# Netfrequency.net
KiCad netlist of a schematic drawn in EAGLE
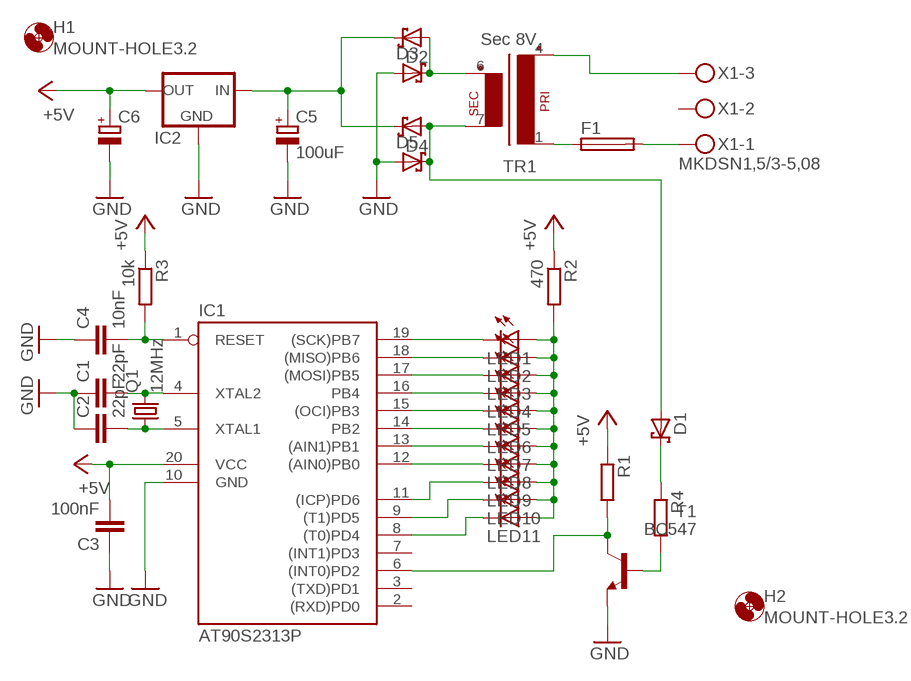
[diagram p0: schematic, sheet 1]

(export (version "E")
  (design (tool "Eeschema 10.0.6"))
  (components
    (comp (ref "C1")
      (value "22pF")
      (footprint "eagle-import:C025-025X050")
      (libsource (lib "eagle-import") (part "C-EU025-025X050"))
    )
    (comp (ref "C2")
      (value "22pF")
      (footprint "eagle-import:C025-025X050")
      (libsource (lib "eagle-import") (part "C-EU025-025X050"))
    )
    (comp (ref "C3")
      (value "100nF")
      (footprint "eagle-import:C025-025X050")
      (libsource (lib "eagle-import") (part "C-EU025-025X050"))
    )
    (comp (ref "C4")
      (value "10nF")
      (footprint "eagle-import:C025-025X050")
      (libsource (lib "eagle-import") (part "C-EU025-025X050"))
    )
    (comp (ref "C5")
      (value "100uF")
      (footprint "eagle-import:E5-8,5")
      (libsource (lib "eagle-import") (part "CPOL-EUE5-8.5"))
    )
    (comp (ref "C6")
      (value "CPOL-EUE2.5-6")
      (footprint "eagle-import:E2,5-6")
      (libsource (lib "eagle-import") (part "CPOL-EUE2.5-6"))
    )
    (comp (ref "D1")
      (value "SCHOTTKY-DIODEDO35-7")
      (footprint "eagle-import:DO35-7")
      (libsource (lib "eagle-import") (part "SCHOTTKY-DIODEDO35-7"))
    )
    (comp (ref "D2")
      (value "SCHOTTKY-DIODEDO35-7")
      (footprint "eagle-import:DO35-7")
      (libsource (lib "eagle-import") (part "SCHOTTKY-DIODEDO35-7"))
    )
    (comp (ref "D3")
      (value "SCHOTTKY-DIODEDO35-7")
      (footprint "eagle-import:DO35-7")
      (libsource (lib "eagle-import") (part "SCHOTTKY-DIODEDO35-7"))
    )
    (comp (ref "D4")
      (value "SCHOTTKY-DIODEDO35-7")
      (footprint "eagle-import:DO35-7")
      (libsource (lib "eagle-import") (part "SCHOTTKY-DIODEDO35-7"))
    )
    (comp (ref "D5")
      (value "SCHOTTKY-DIODEDO35-7")
      (footprint "eagle-import:DO35-7")
      (libsource (lib "eagle-import") (part "SCHOTTKY-DIODEDO35-7"))
    )
    (comp (ref "F1")
      (value "SH22")
      (footprint "eagle-import:SH22")
      (libsource (lib "eagle-import") (part "SH22"))
    )
    (comp (ref "H1")
      (value "MOUNT-HOLE3.2")
      (footprint "eagle-import:3,2")
      (libsource (lib "eagle-import") (part "MOUNT-HOLE3.2"))
    )
    (comp (ref "H2")
      (value "MOUNT-HOLE3.2")
      (footprint "eagle-import:3,2")
      (libsource (lib "eagle-import") (part "MOUNT-HOLE3.2"))
    )
    (comp (ref "IC1")
      (value "AT90S2313P")
      (footprint "eagle-import:DIL20")
      (libsource (lib "eagle-import") (part "AT90S2313P"))
    )
    (comp (ref "IC2")
      (value "78LXX")
      (footprint "eagle-import:78LXX")
      (libsource (lib "eagle-import") (part "78LXX"))
    )
    (comp (ref "LED1")
      (value "LEDSQR2X5")
      (footprint "eagle-import:LED2X5")
      (libsource (lib "eagle-import") (part "LEDSQR2X5"))
    )
    (comp (ref "LED2")
      (value "LEDSQR2X5")
      (footprint "eagle-import:LED2X5")
      (libsource (lib "eagle-import") (part "LEDSQR2X5"))
    )
    (comp (ref "LED3")
      (value "LEDSQR2X5")
      (footprint "eagle-import:LED2X5")
      (libsource (lib "eagle-import") (part "LEDSQR2X5"))
    )
    (comp (ref "LED4")
      (value "LEDSQR2X5")
      (footprint "eagle-import:LED2X5")
      (libsource (lib "eagle-import") (part "LEDSQR2X5"))
    )
    (comp (ref "LED5")
      (value "LEDSQR2X5")
      (footprint "eagle-import:LED2X5")
      (libsource (lib "eagle-import") (part "LEDSQR2X5"))
    )
    (comp (ref "LED6")
      (value "LEDSQR2X5")
      (footprint "eagle-import:LED2X5")
      (libsource (lib "eagle-import") (part "LEDSQR2X5"))
    )
    (comp (ref "LED7")
      (value "LEDSQR2X5")
      (footprint "eagle-import:LED2X5")
      (libsource (lib "eagle-import") (part "LEDSQR2X5"))
    )
    (comp (ref "LED8")
      (value "LEDSQR2X5")
      (footprint "eagle-import:LED2X5")
      (libsource (lib "eagle-import") (part "LEDSQR2X5"))
    )
    (comp (ref "LED9")
      (value "LEDSQR2X5")
      (footprint "eagle-import:LED2X5")
      (libsource (lib "eagle-import") (part "LEDSQR2X5"))
    )
    (comp (ref "LED10")
      (value "LEDSQR2X5")
      (footprint "eagle-import:LED2X5")
      (libsource (lib "eagle-import") (part "LEDSQR2X5"))
    )
    (comp (ref "LED11")
      (value "LEDSQR2X5")
      (footprint "eagle-import:LED2X5")
      (libsource (lib "eagle-import") (part "LEDSQR2X5"))
    )
    (comp (ref "Q1")
      (value "12MHz")
      (footprint "eagle-import:HC49_S")
      (libsource (lib "eagle-import") (part "CRYSTALHC49S"))
    )
    (comp (ref "R1")
      (value "R-EU_0204/7")
      (footprint "eagle-import:0204_7")
      (libsource (lib "eagle-import") (part "R-EU_0204/7"))
    )
    (comp (ref "R2")
      (value "470")
      (footprint "eagle-import:0204_7")
      (libsource (lib "eagle-import") (part "R-EU_0204/7"))
    )
    (comp (ref "R3")
      (value "10k")
      (footprint "eagle-import:0204_7")
      (libsource (lib "eagle-import") (part "R-EU_0204/7"))
    )
    (comp (ref "R4")
      (value "R-EU_0204/7")
      (footprint "eagle-import:0204_7")
      (libsource (lib "eagle-import") (part "R-EU_0204/7"))
    )
    (comp (ref "T1")
      (value "BC547")
      (footprint "eagle-import:TO92")
      (libsource (lib "eagle-import") (part "BC547"))
    )
    (comp (ref "TR1")
      (value "Sec 8V")
      (footprint "eagle-import:EE20-1")
      (libsource (lib "eagle-import") (part "EE20-1"))
    )
    (comp (ref "X1")
      (value "MKDSN1,5/3-5,08")
      (footprint "eagle-import:MKDSN1,5_3-5,08")
      (fields (field (name "MPN") "SMKDSN1,5/3-5,08"))
      (libsource (lib "eagle-import") (part "MKDSN1,5/3-5,08"))
    )
  )
  (nets
    (net (code "1") (name "+5V") (class "Default")
      (node (ref "C3") (pin "2") (pinfunction "2_2") (pintype "passive"))
      (node (ref "C6") (pin "+") (pinfunction "+_+") (pintype "passive"))
      (node (ref "IC1") (pin "20") (pinfunction "VCC_20") (pintype "power_in"))
      (node (ref "IC2") (pin "OUT") (pinfunction "OUT_OUT") (pintype "passive"))
      (node (ref "R1") (pin "1") (pinfunction "1_1") (pintype "passive"))
      (node (ref "R2") (pin "1") (pinfunction "1_1") (pintype "passive"))
      (node (ref "R3") (pin "1") (pinfunction "1_1") (pintype "passive"))
    )
    (net (code "2") (name "GND") (class "Default")
      (node (ref "C1") (pin "1") (pinfunction "1_1") (pintype "passive"))
      (node (ref "C2") (pin "1") (pinfunction "1_1") (pintype "passive"))
      (node (ref "C3") (pin "1") (pinfunction "1_1") (pintype "passive"))
      (node (ref "C4") (pin "1") (pinfunction "1_1") (pintype "passive"))
      (node (ref "C5") (pin "-") (pinfunction "-_-") (pintype "passive"))
      (node (ref "C6") (pin "-") (pinfunction "-_-") (pintype "passive"))
      (node (ref "D3") (pin "A") (pinfunction "A_A") (pintype "passive"))
      (node (ref "D5") (pin "A") (pinfunction "A_A") (pintype "passive"))
      (node (ref "IC1") (pin "10") (pinfunction "GND_10") (pintype "power_in"))
      (node (ref "IC2") (pin "GND") (pinfunction "GND_GND") (pintype "input"))
      (node (ref "T1") (pin "1") (pinfunction "E_1") (pintype "passive"))
    )
    (net (code "3") (name "Net-(C5-Pad+)") (class "Default")
      (node (ref "C5") (pin "+") (pinfunction "+_+") (pintype "passive"))
      (node (ref "D2") (pin "C") (pinfunction "C_C") (pintype "passive"))
      (node (ref "D4") (pin "C") (pinfunction "C_C") (pintype "passive"))
      (node (ref "IC2") (pin "IN") (pinfunction "IN_IN") (pintype "input"))
    )
    (net (code "4") (name "Net-(D1-PadC)") (class "Default")
      (node (ref "D1") (pin "C") (pinfunction "C_C") (pintype "passive"))
      (node (ref "R4") (pin "1") (pinfunction "1_1") (pintype "passive"))
    )
    (net (code "5") (name "Net-(IC1-(AIN0)PB0)") (class "Default")
      (node (ref "IC1") (pin "12") (pinfunction "(AIN0)PB0_12") (pintype "bidirectional"))
      (node (ref "LED8") (pin "K") (pinfunction "C_K") (pintype "passive"))
    )
    (net (code "6") (name "Net-(IC1-(AIN1)PB1)") (class "Default")
      (node (ref "IC1") (pin "13") (pinfunction "(AIN1)PB1_13") (pintype "bidirectional"))
      (node (ref "LED7") (pin "K") (pinfunction "C_K") (pintype "passive"))
    )
    (net (code "7") (name "Net-(IC1-(ICP)PD6)") (class "Default")
      (node (ref "IC1") (pin "11") (pinfunction "(ICP)PD6_11") (pintype "bidirectional"))
      (node (ref "LED9") (pin "K") (pinfunction "C_K") (pintype "passive"))
    )
    (net (code "8") (name "Net-(IC1-(INT0)PD2)") (class "Default")
      (node (ref "IC1") (pin "6") (pinfunction "(INT0)PD2_6") (pintype "bidirectional"))
      (node (ref "R1") (pin "2") (pinfunction "2_2") (pintype "passive"))
      (node (ref "T1") (pin "3") (pinfunction "C_3") (pintype "passive"))
    )
    (net (code "9") (name "Net-(IC1-(MISO)PB6)") (class "Default")
      (node (ref "IC1") (pin "18") (pinfunction "(MISO)PB6_18") (pintype "bidirectional"))
      (node (ref "LED2") (pin "K") (pinfunction "C_K") (pintype "passive"))
    )
    (net (code "10") (name "Net-(IC1-(MOSI)PB5)") (class "Default")
      (node (ref "IC1") (pin "17") (pinfunction "(MOSI)PB5_17") (pintype "bidirectional"))
      (node (ref "LED3") (pin "K") (pinfunction "C_K") (pintype "passive"))
    )
    (net (code "11") (name "Net-(IC1-(OCI)PB3)") (class "Default")
      (node (ref "IC1") (pin "15") (pinfunction "(OCI)PB3_15") (pintype "bidirectional"))
      (node (ref "LED5") (pin "K") (pinfunction "C_K") (pintype "passive"))
    )
    (net (code "12") (name "Net-(IC1-(SCK)PB7)") (class "Default")
      (node (ref "IC1") (pin "19") (pinfunction "(SCK)PB7_19") (pintype "bidirectional"))
      (node (ref "LED1") (pin "K") (pinfunction "C_K") (pintype "passive"))
    )
    (net (code "13") (name "Net-(IC1-(T0)PD4)") (class "Default")
      (node (ref "IC1") (pin "8") (pinfunction "(T0)PD4_8") (pintype "bidirectional"))
      (node (ref "LED11") (pin "K") (pinfunction "C_K") (pintype "passive"))
    )
    (net (code "14") (name "Net-(IC1-(T1)PD5)") (class "Default")
      (node (ref "IC1") (pin "9") (pinfunction "(T1)PD5_9") (pintype "bidirectional"))
      (node (ref "LED10") (pin "K") (pinfunction "C_K") (pintype "passive"))
    )
    (net (code "15") (name "Net-(IC1-PB2)") (class "Default")
      (node (ref "IC1") (pin "14") (pinfunction "PB2_14") (pintype "bidirectional"))
      (node (ref "LED6") (pin "K") (pinfunction "C_K") (pintype "passive"))
    )
    (net (code "16") (name "Net-(IC1-PB4)") (class "Default")
      (node (ref "IC1") (pin "16") (pinfunction "PB4_16") (pintype "bidirectional"))
      (node (ref "LED4") (pin "K") (pinfunction "C_K") (pintype "passive"))
    )
    (net (code "17") (name "Net-(IC1-RESET)") (class "Default")
      (node (ref "C4") (pin "2") (pinfunction "2_2") (pintype "passive"))
      (node (ref "IC1") (pin "1") (pinfunction "RESET_1") (pintype "bidirectional"))
      (node (ref "R3") (pin "2") (pinfunction "2_2") (pintype "passive"))
    )
    (net (code "18") (name "Net-(IC1-XTAL1)") (class "Default")
      (node (ref "C2") (pin "2") (pinfunction "2_2") (pintype "passive"))
      (node (ref "IC1") (pin "5") (pinfunction "XTAL1_5") (pintype "bidirectional"))
      (node (ref "Q1") (pin "1") (pinfunction "1_1") (pintype "passive"))
    )
    (net (code "19") (name "Net-(IC1-XTAL2)") (class "Default")
      (node (ref "C1") (pin "2") (pinfunction "2_2") (pintype "passive"))
      (node (ref "IC1") (pin "4") (pinfunction "XTAL2_4") (pintype "bidirectional"))
      (node (ref "Q1") (pin "2") (pinfunction "2_2") (pintype "passive"))
    )
    (net (code "20") (name "Net-(LED1-PadA)") (class "Default")
      (node (ref "LED1") (pin "A") (pinfunction "A_A") (pintype "passive"))
      (node (ref "LED10") (pin "A") (pinfunction "A_A") (pintype "passive"))
      (node (ref "LED11") (pin "A") (pinfunction "A_A") (pintype "passive"))
      (node (ref "LED2") (pin "A") (pinfunction "A_A") (pintype "passive"))
      (node (ref "LED3") (pin "A") (pinfunction "A_A") (pintype "passive"))
      (node (ref "LED4") (pin "A") (pinfunction "A_A") (pintype "passive"))
      (node (ref "LED5") (pin "A") (pinfunction "A_A") (pintype "passive"))
      (node (ref "LED6") (pin "A") (pinfunction "A_A") (pintype "passive"))
      (node (ref "LED7") (pin "A") (pinfunction "A_A") (pintype "passive"))
      (node (ref "LED8") (pin "A") (pinfunction "A_A") (pintype "passive"))
      (node (ref "LED9") (pin "A") (pinfunction "A_A") (pintype "passive"))
      (node (ref "R2") (pin "2") (pinfunction "2_2") (pintype "passive"))
    )
    (net (code "21") (name "Net-(T1-B)") (class "Default")
      (node (ref "R4") (pin "2") (pinfunction "2_2") (pintype "passive"))
      (node (ref "T1") (pin "2") (pinfunction "B_2") (pintype "passive"))
    )
    (net (code "22") (name "Net-(TR1-P1)") (class "Default")
      (node (ref "F1") (pin "1") (pinfunction "1_1") (pintype "passive"))
      (node (ref "TR1") (pin "1") (pinfunction "P1_1") (pintype "passive"))
    )
    (net (code "23") (name "Net-(TR1-P2)") (class "Default")
      (node (ref "TR1") (pin "4") (pinfunction "P2_4") (pintype "passive"))
      (node (ref "X1") (pin "3") (pinfunction "KL_3") (pintype "passive"))
    )
    (net (code "24") (name "Net-(TR1-S3)") (class "Default")
      (node (ref "D2") (pin "A") (pinfunction "A_A") (pintype "passive"))
      (node (ref "D3") (pin "C") (pinfunction "C_C") (pintype "passive"))
      (node (ref "TR1") (pin "6") (pinfunction "S3_6") (pintype "passive"))
    )
    (net (code "25") (name "Net-(TR1-S4)") (class "Default")
      (node (ref "D1") (pin "A") (pinfunction "A_A") (pintype "passive"))
      (node (ref "D4") (pin "A") (pinfunction "A_A") (pintype "passive"))
      (node (ref "D5") (pin "C") (pinfunction "C_C") (pintype "passive"))
      (node (ref "TR1") (pin "7") (pinfunction "S4_7") (pintype "passive"))
    )
    (net (code "26") (name "Net-(X1A-KL)") (class "Default")
      (node (ref "F1") (pin "2") (pinfunction "2_2") (pintype "passive"))
      (node (ref "X1") (pin "1") (pinfunction "KL_1") (pintype "passive"))
    )
    (net (code "27") (name "unconnected-(IC1-(INT1)PD3-Pad7)") (class "Default")
      (node (ref "IC1") (pin "7") (pinfunction "(INT1)PD3_7") (pintype "bidirectional"))
    )
    (net (code "28") (name "unconnected-(IC1-(RXD)PD0-Pad2)") (class "Default")
      (node (ref "IC1") (pin "2") (pinfunction "(RXD)PD0_2") (pintype "bidirectional"))
    )
    (net (code "29") (name "unconnected-(IC1-(TXD)PD1-Pad3)") (class "Default")
      (node (ref "IC1") (pin "3") (pinfunction "(TXD)PD1_3") (pintype "bidirectional"))
    )
    (net (code "30") (name "unconnected-(X1B-KL-Pad2)") (class "Default")
      (node (ref "X1") (pin "2") (pinfunction "KL_2") (pintype "passive"))
    )
  )
)
